# qtpy_synth_proto2a.net
KiCad netlist of a schematic drawn in EAGLE
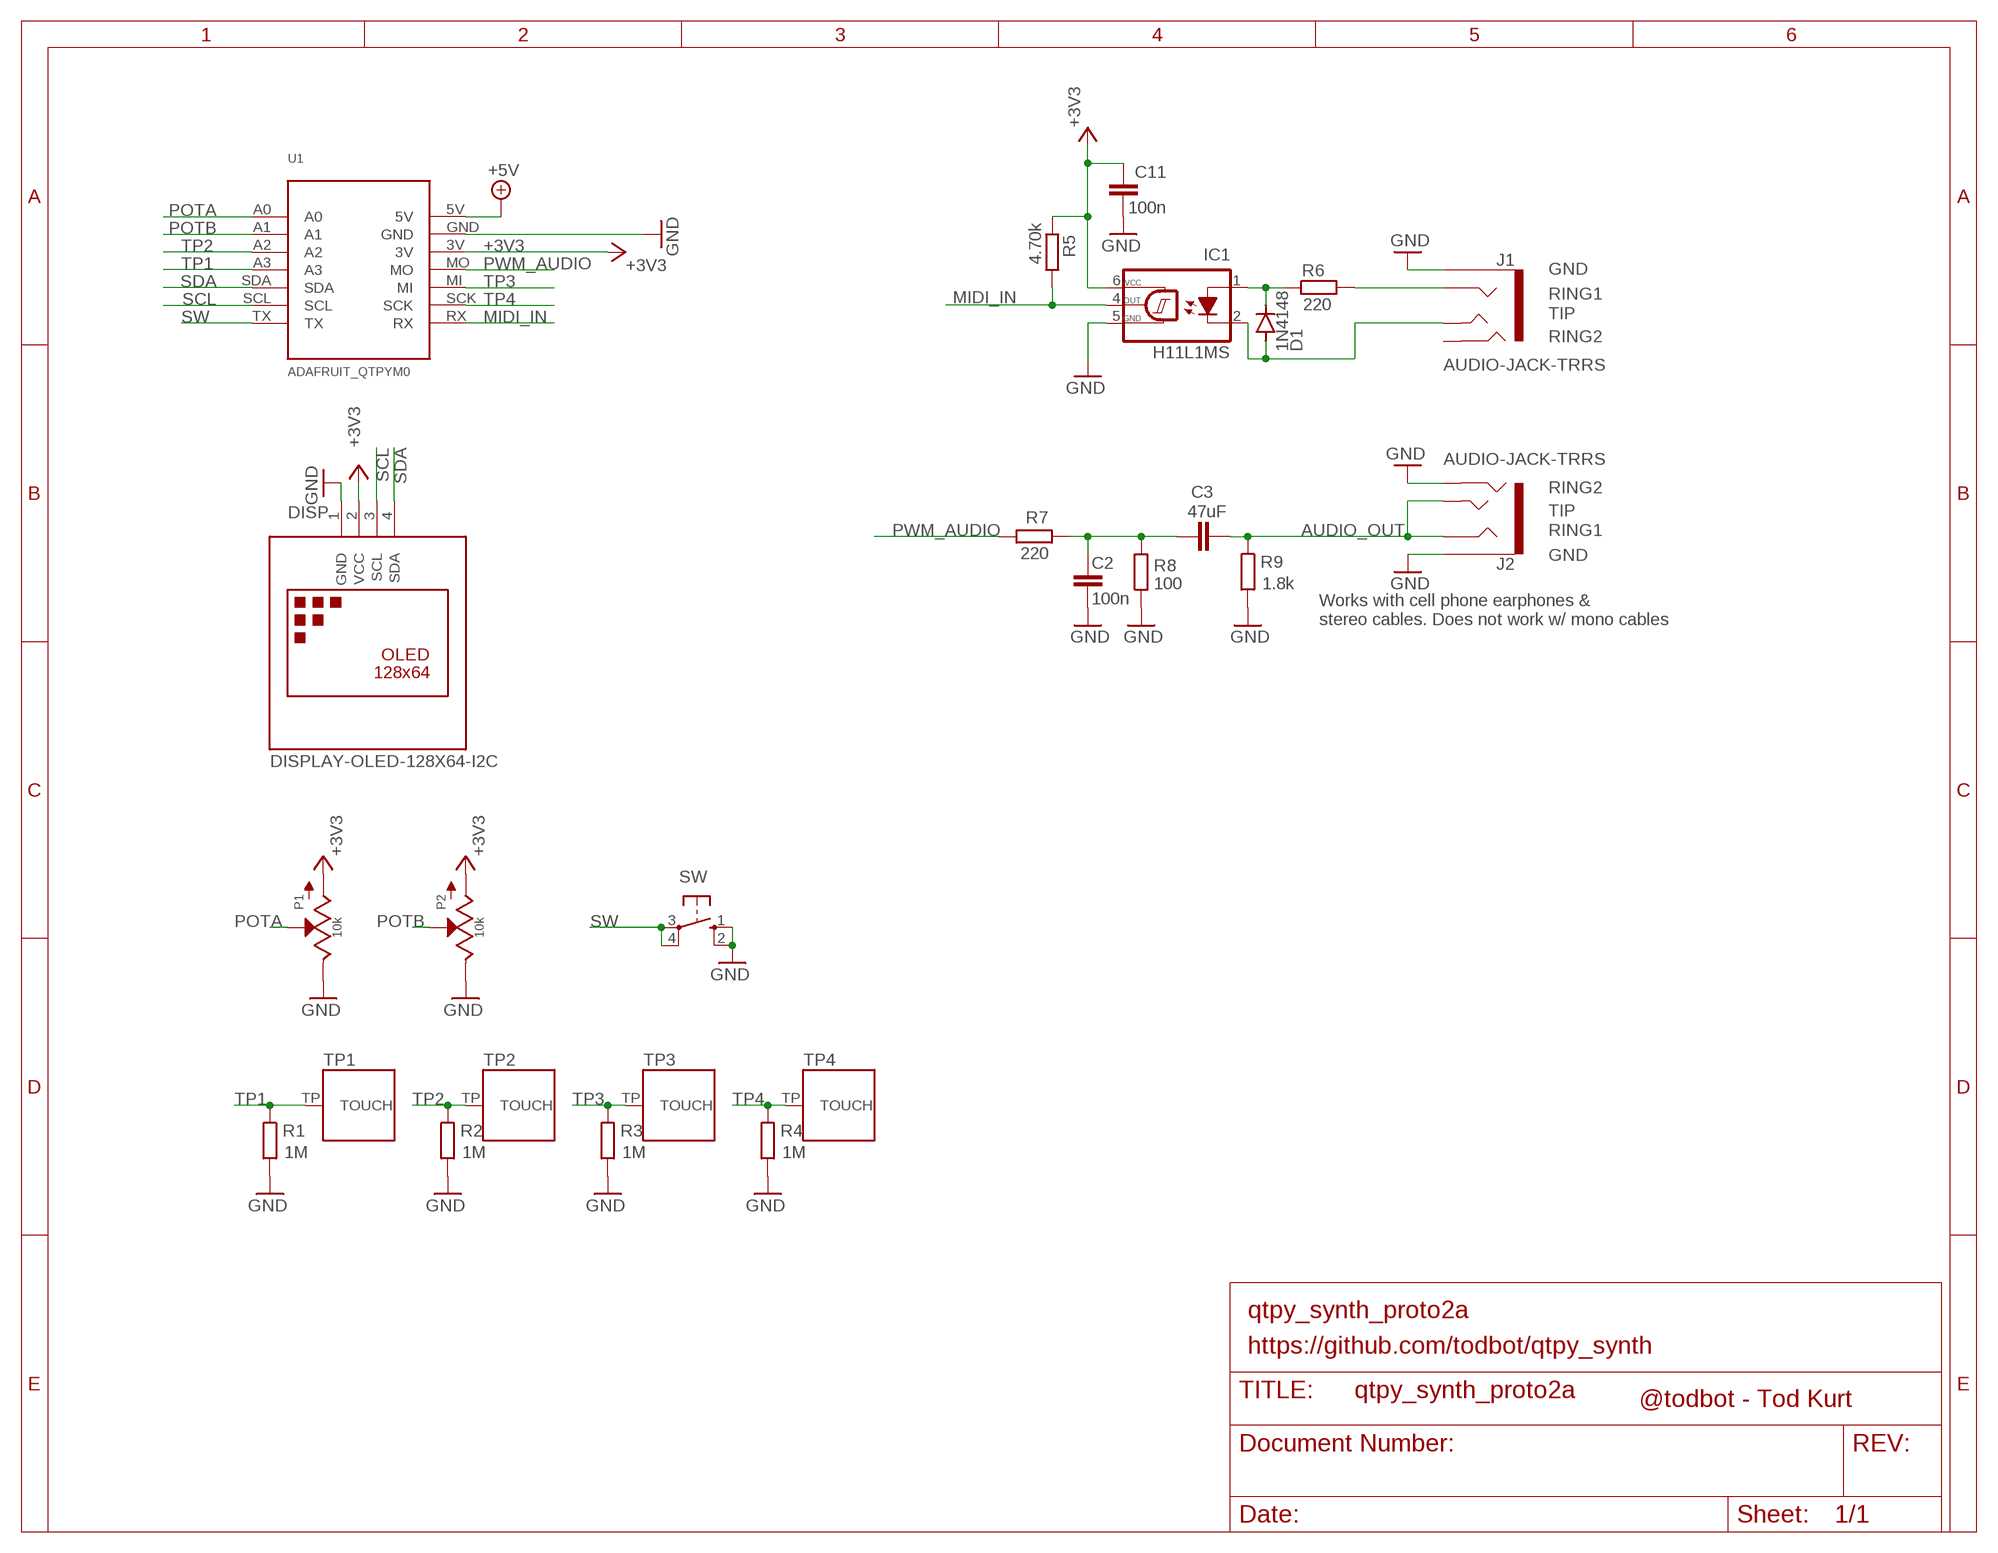
[diagram p0: schematic, sheet 1]

(export (version "E")
  (design (tool "Eeschema 10.0.6"))
  (components
    (comp (ref "C2")
      (value "100n")
      (footprint "eagle-import:C0805")
      (libsource (lib "eagle-import") (part "C-EUC0805"))
    )
    (comp (ref "C3")
      (value "47uF")
      (footprint "eagle-import:C0805")
      (libsource (lib "eagle-import") (part "C-EUC0805"))
    )
    (comp (ref "C11")
      (value "100n")
      (footprint "eagle-import:C0805")
      (libsource (lib "eagle-import") (part "C-EUC0805"))
    )
    (comp (ref "D1")
      (value "1N4148")
      (footprint "eagle-import:SOD123")
      (libsource (lib "eagle-import") (part "DIODE-SOD123"))
    )
    (comp (ref "DISP")
      (value "DISPLAY-OLED-128X64-I2C")
      (footprint "eagle-import:DISPLAY-OLED-128X64-I2C")
      (libsource (lib "eagle-import") (part "DISPLAY-OLED-128X64-I2C"))
    )
    (comp (ref "IC1")
      (value "H11L1MS")
      (footprint "eagle-import:DIL6-SMD")
      (libsource (lib "eagle-import") (part "H11LMS1"))
    )
    (comp (ref "J1")
      (value "AUDIO-JACK-TRRS")
      (footprint "eagle-import:PJ-320D_SPARKFUN")
      (fields (field (name "MPN") "PJ-320D"))
      (libsource (lib "eagle-import") (part "AUDIO-JACK-TRRS"))
    )
    (comp (ref "J2")
      (value "AUDIO-JACK-TRRS")
      (footprint "eagle-import:PJ-320D_SPARKFUN")
      (fields (field (name "MPN") "PJ-320D") (field (name "LCSC") "C431535"))
      (libsource (lib "eagle-import") (part "AUDIO-JACK-TRRS"))
    )
    (comp (ref "P1")
      (value "10k")
      (footprint "eagle-import:OG-POTS_ALPS_POT_VERTICAL_WITHBIGKNOB")
      (libsource (lib "eagle-import") (part "POTZEPHPOT_BIGKNOB"))
    )
    (comp (ref "P2")
      (value "10k")
      (footprint "eagle-import:OG-POTS_ALPS_POT_VERTICAL_WITHBIGKNOB")
      (libsource (lib "eagle-import") (part "POTZEPHPOT_BIGKNOB"))
    )
    (comp (ref "R1")
      (value "1M")
      (footprint "eagle-import:R0805")
      (libsource (lib "eagle-import") (part "R-EU_R0805"))
    )
    (comp (ref "R2")
      (value "1M")
      (footprint "eagle-import:R0805")
      (libsource (lib "eagle-import") (part "R-EU_R0805"))
    )
    (comp (ref "R3")
      (value "1M")
      (footprint "eagle-import:R0805")
      (libsource (lib "eagle-import") (part "R-EU_R0805"))
    )
    (comp (ref "R4")
      (value "1M")
      (footprint "eagle-import:R0805")
      (libsource (lib "eagle-import") (part "R-EU_R0805"))
    )
    (comp (ref "R5")
      (value "4.70k")
      (footprint "eagle-import:R0805")
      (libsource (lib "eagle-import") (part "R-EU_R0805"))
    )
    (comp (ref "R6")
      (value "220")
      (footprint "eagle-import:R0805")
      (libsource (lib "eagle-import") (part "R-EU_R0805"))
    )
    (comp (ref "R7")
      (value "220")
      (footprint "eagle-import:R0805")
      (libsource (lib "eagle-import") (part "R-EU_R0805"))
    )
    (comp (ref "R8")
      (value "100")
      (footprint "eagle-import:R0805")
      (libsource (lib "eagle-import") (part "R-EU_R0805"))
    )
    (comp (ref "R9")
      (value "1.8k")
      (footprint "eagle-import:R0805")
      (libsource (lib "eagle-import") (part "R-EU_R0805"))
    )
    (comp (ref "SW")
      (value "10-XX")
      (footprint "eagle-import:B3F-10XX")
      (fields (field (name "MPN") "B3F-1000"))
      (libsource (lib "eagle-import") (part "10-XX"))
    )
    (comp (ref "TP1")
      (value "TOUCHPADA")
      (footprint "eagle-import:TOUCHPADA_0.5IN")
      (libsource (lib "eagle-import") (part "TOUCHPADA"))
    )
    (comp (ref "TP2")
      (value "TOUCHPADA")
      (footprint "eagle-import:TOUCHPADA_0.5IN")
      (libsource (lib "eagle-import") (part "TOUCHPADA"))
    )
    (comp (ref "TP3")
      (value "TOUCHPADA")
      (footprint "eagle-import:TOUCHPADA_0.5IN")
      (libsource (lib "eagle-import") (part "TOUCHPADA"))
    )
    (comp (ref "TP4")
      (value "TOUCHPADA")
      (footprint "eagle-import:TOUCHPADA_0.5IN")
      (libsource (lib "eagle-import") (part "TOUCHPADA"))
    )
    (comp (ref "U1")
      (value "ADAFRUIT_QTPYM0")
      (footprint "eagle-import:ADAFRUIT_QTPY_M0")
      (libsource (lib "eagle-import") (part "ADAFRUIT_QTPYM0"))
    )
  )
  (nets
    (net (code "1") (name "+3V3") (class "Default")
      (node (ref "C11") (pin "1") (pinfunction "1_1") (pintype "passive"))
      (node (ref "DISP") (pin "2") (pinfunction "VCC_2") (pintype "power_in"))
      (node (ref "IC1") (pin "6") (pinfunction "VCC_6") (pintype "power_in"))
      (node (ref "P1") (pin "P$3") (pinfunction "A_P$3") (pintype "passive"))
      (node (ref "P2") (pin "P$3") (pinfunction "A_P$3") (pintype "passive"))
      (node (ref "R5") (pin "1") (pinfunction "1_1") (pintype "passive"))
      (node (ref "U1") (pin "3V") (pinfunction "3V_3V") (pintype "bidirectional"))
    )
    (net (code "2") (name "+5V") (class "Default")
      (node (ref "U1") (pin "5V") (pinfunction "5V_5V") (pintype "bidirectional"))
    )
    (net (code "3") (name "/AUDIO_OUT") (class "Default")
      (node (ref "C3") (pin "2") (pinfunction "2_2") (pintype "passive"))
      (node (ref "J2") (pin "RING1") (pinfunction "RING1_RING1") (pintype "bidirectional"))
      (node (ref "J2") (pin "TIP") (pinfunction "TIP_TIP") (pintype "bidirectional"))
      (node (ref "R9") (pin "1") (pinfunction "1_1") (pintype "passive"))
    )
    (net (code "4") (name "/MIDI_IN") (class "Default")
      (node (ref "IC1") (pin "4") (pinfunction "OUT_4") (pintype "output"))
      (node (ref "R5") (pin "2") (pinfunction "2_2") (pintype "passive"))
      (node (ref "U1") (pin "RX") (pinfunction "RX_RX") (pintype "bidirectional"))
    )
    (net (code "5") (name "/POTA") (class "Default")
      (node (ref "P1") (pin "P$2") (pinfunction "S_P$2") (pintype "passive"))
      (node (ref "U1") (pin "A0") (pinfunction "A0_A0") (pintype "bidirectional"))
    )
    (net (code "6") (name "/POTB") (class "Default")
      (node (ref "P2") (pin "P$2") (pinfunction "S_P$2") (pintype "passive"))
      (node (ref "U1") (pin "A1") (pinfunction "A1_A1") (pintype "bidirectional"))
    )
    (net (code "7") (name "/PWM_AUDIO") (class "Default")
      (node (ref "R7") (pin "2") (pinfunction "2_2") (pintype "passive"))
      (node (ref "U1") (pin "MO") (pinfunction "MO_MO") (pintype "bidirectional"))
    )
    (net (code "8") (name "/SCL") (class "Default")
      (node (ref "DISP") (pin "3") (pinfunction "SCL_3") (pintype "bidirectional"))
      (node (ref "U1") (pin "SCL") (pinfunction "SCL_SCL") (pintype "bidirectional"))
    )
    (net (code "9") (name "/SDA") (class "Default")
      (node (ref "DISP") (pin "4") (pinfunction "SDA_4") (pintype "bidirectional"))
      (node (ref "U1") (pin "SDA") (pinfunction "SDA_SDA") (pintype "bidirectional"))
    )
    (net (code "10") (name "/SW") (class "Default")
      (node (ref "SW") (pin "3") (pinfunction "P_3") (pintype "passive"))
      (node (ref "SW") (pin "4") (pinfunction "P1_4") (pintype "passive"))
      (node (ref "U1") (pin "TX") (pinfunction "TX_TX") (pintype "bidirectional"))
    )
    (net (code "11") (name "/TP1") (class "Default")
      (node (ref "R1") (pin "1") (pinfunction "1_1") (pintype "passive"))
      (node (ref "TP1") (pin "TP") (pinfunction "TOUCH_TP") (pintype "bidirectional"))
      (node (ref "U1") (pin "A3") (pinfunction "A3_A3") (pintype "bidirectional"))
    )
    (net (code "12") (name "/TP2") (class "Default")
      (node (ref "R2") (pin "1") (pinfunction "1_1") (pintype "passive"))
      (node (ref "TP2") (pin "TP") (pinfunction "TOUCH_TP") (pintype "bidirectional"))
      (node (ref "U1") (pin "A2") (pinfunction "A2_A2") (pintype "bidirectional"))
    )
    (net (code "13") (name "/TP3") (class "Default")
      (node (ref "R3") (pin "1") (pinfunction "1_1") (pintype "passive"))
      (node (ref "TP3") (pin "TP") (pinfunction "TOUCH_TP") (pintype "bidirectional"))
      (node (ref "U1") (pin "MI") (pinfunction "MI_MI") (pintype "bidirectional"))
    )
    (net (code "14") (name "/TP4") (class "Default")
      (node (ref "R4") (pin "1") (pinfunction "1_1") (pintype "passive"))
      (node (ref "TP4") (pin "TP") (pinfunction "TOUCH_TP") (pintype "bidirectional"))
      (node (ref "U1") (pin "SCK") (pinfunction "SCK_SCK") (pintype "bidirectional"))
    )
    (net (code "15") (name "GND") (class "Default")
      (node (ref "C11") (pin "2") (pinfunction "2_2") (pintype "passive"))
      (node (ref "C2") (pin "2") (pinfunction "2_2") (pintype "passive"))
      (node (ref "DISP") (pin "1") (pinfunction "GND_1") (pintype "power_in"))
      (node (ref "IC1") (pin "5") (pinfunction "GND_5") (pintype "power_in"))
      (node (ref "J1") (pin "EARTH") (pinfunction "EARTH_EARTH") (pintype "bidirectional"))
      (node (ref "J2") (pin "EARTH") (pinfunction "EARTH_EARTH") (pintype "bidirectional"))
      (node (ref "J2") (pin "RING2") (pinfunction "RING2_RING2") (pintype "bidirectional"))
      (node (ref "P1") (pin "P$1") (pinfunction "E_P$1") (pintype "passive"))
      (node (ref "P2") (pin "P$1") (pinfunction "E_P$1") (pintype "passive"))
      (node (ref "R1") (pin "2") (pinfunction "2_2") (pintype "passive"))
      (node (ref "R2") (pin "2") (pinfunction "2_2") (pintype "passive"))
      (node (ref "R3") (pin "2") (pinfunction "2_2") (pintype "passive"))
      (node (ref "R4") (pin "2") (pinfunction "2_2") (pintype "passive"))
      (node (ref "R8") (pin "1") (pinfunction "1_1") (pintype "passive"))
      (node (ref "R9") (pin "2") (pinfunction "2_2") (pintype "passive"))
      (node (ref "SW") (pin "1") (pinfunction "S_1") (pintype "passive"))
      (node (ref "SW") (pin "2") (pinfunction "S1_2") (pintype "passive"))
      (node (ref "U1") (pin "GND") (pinfunction "GND_GND") (pintype "bidirectional"))
    )
    (net (code "16") (name "Net-(C2-Pad1)") (class "Default")
      (node (ref "C2") (pin "1") (pinfunction "1_1") (pintype "passive"))
      (node (ref "C3") (pin "1") (pinfunction "1_1") (pintype "passive"))
      (node (ref "R7") (pin "1") (pinfunction "1_1") (pintype "passive"))
      (node (ref "R8") (pin "2") (pinfunction "2_2") (pintype "passive"))
    )
    (net (code "17") (name "Net-(IC1-A)") (class "Default")
      (node (ref "D1") (pin "C") (pinfunction "C_C") (pintype "passive"))
      (node (ref "IC1") (pin "1") (pinfunction "A_1") (pintype "passive"))
      (node (ref "R6") (pin "1") (pinfunction "1_1") (pintype "passive"))
    )
    (net (code "18") (name "Net-(IC1-C)") (class "Default")
      (node (ref "D1") (pin "A") (pinfunction "A_A") (pintype "passive"))
      (node (ref "IC1") (pin "2") (pinfunction "C_2") (pintype "passive"))
      (node (ref "J1") (pin "TIP") (pinfunction "TIP_TIP") (pintype "bidirectional"))
    )
    (net (code "19") (name "Net-(J1-PadRING1)") (class "Default")
      (node (ref "J1") (pin "RING1") (pinfunction "RING1_RING1") (pintype "bidirectional"))
      (node (ref "R6") (pin "2") (pinfunction "2_2") (pintype "passive"))
    )
    (net (code "20") (name "unconnected-(J1-PadRING2)") (class "Default")
      (node (ref "J1") (pin "RING2") (pinfunction "RING2_RING2") (pintype "bidirectional"))
    )
  )
)
